# chipdesign2018.net
KiCad netlist of a schematic drawn in EAGLE
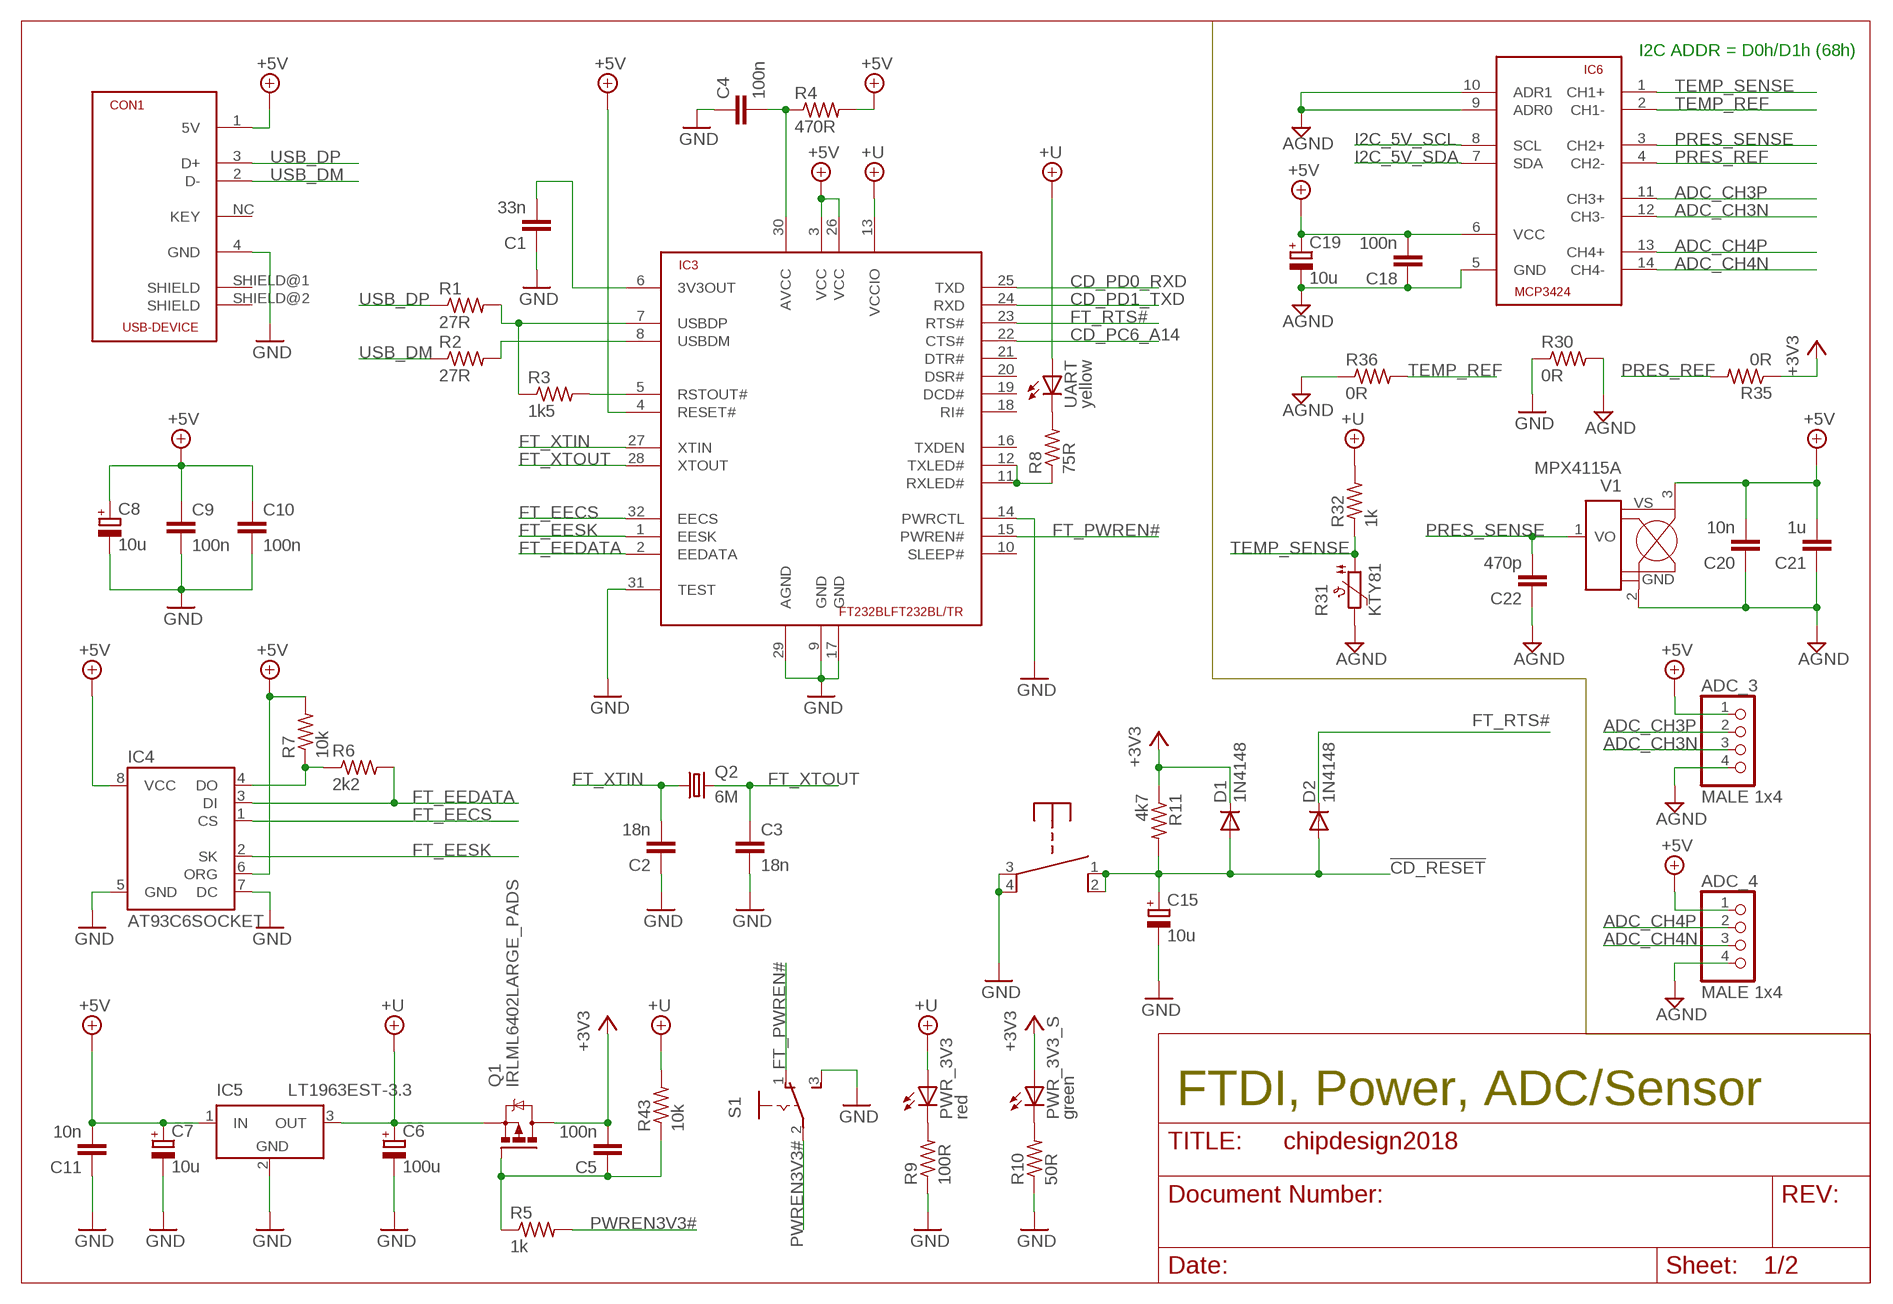
[diagram p0: schematic, sheet 1]
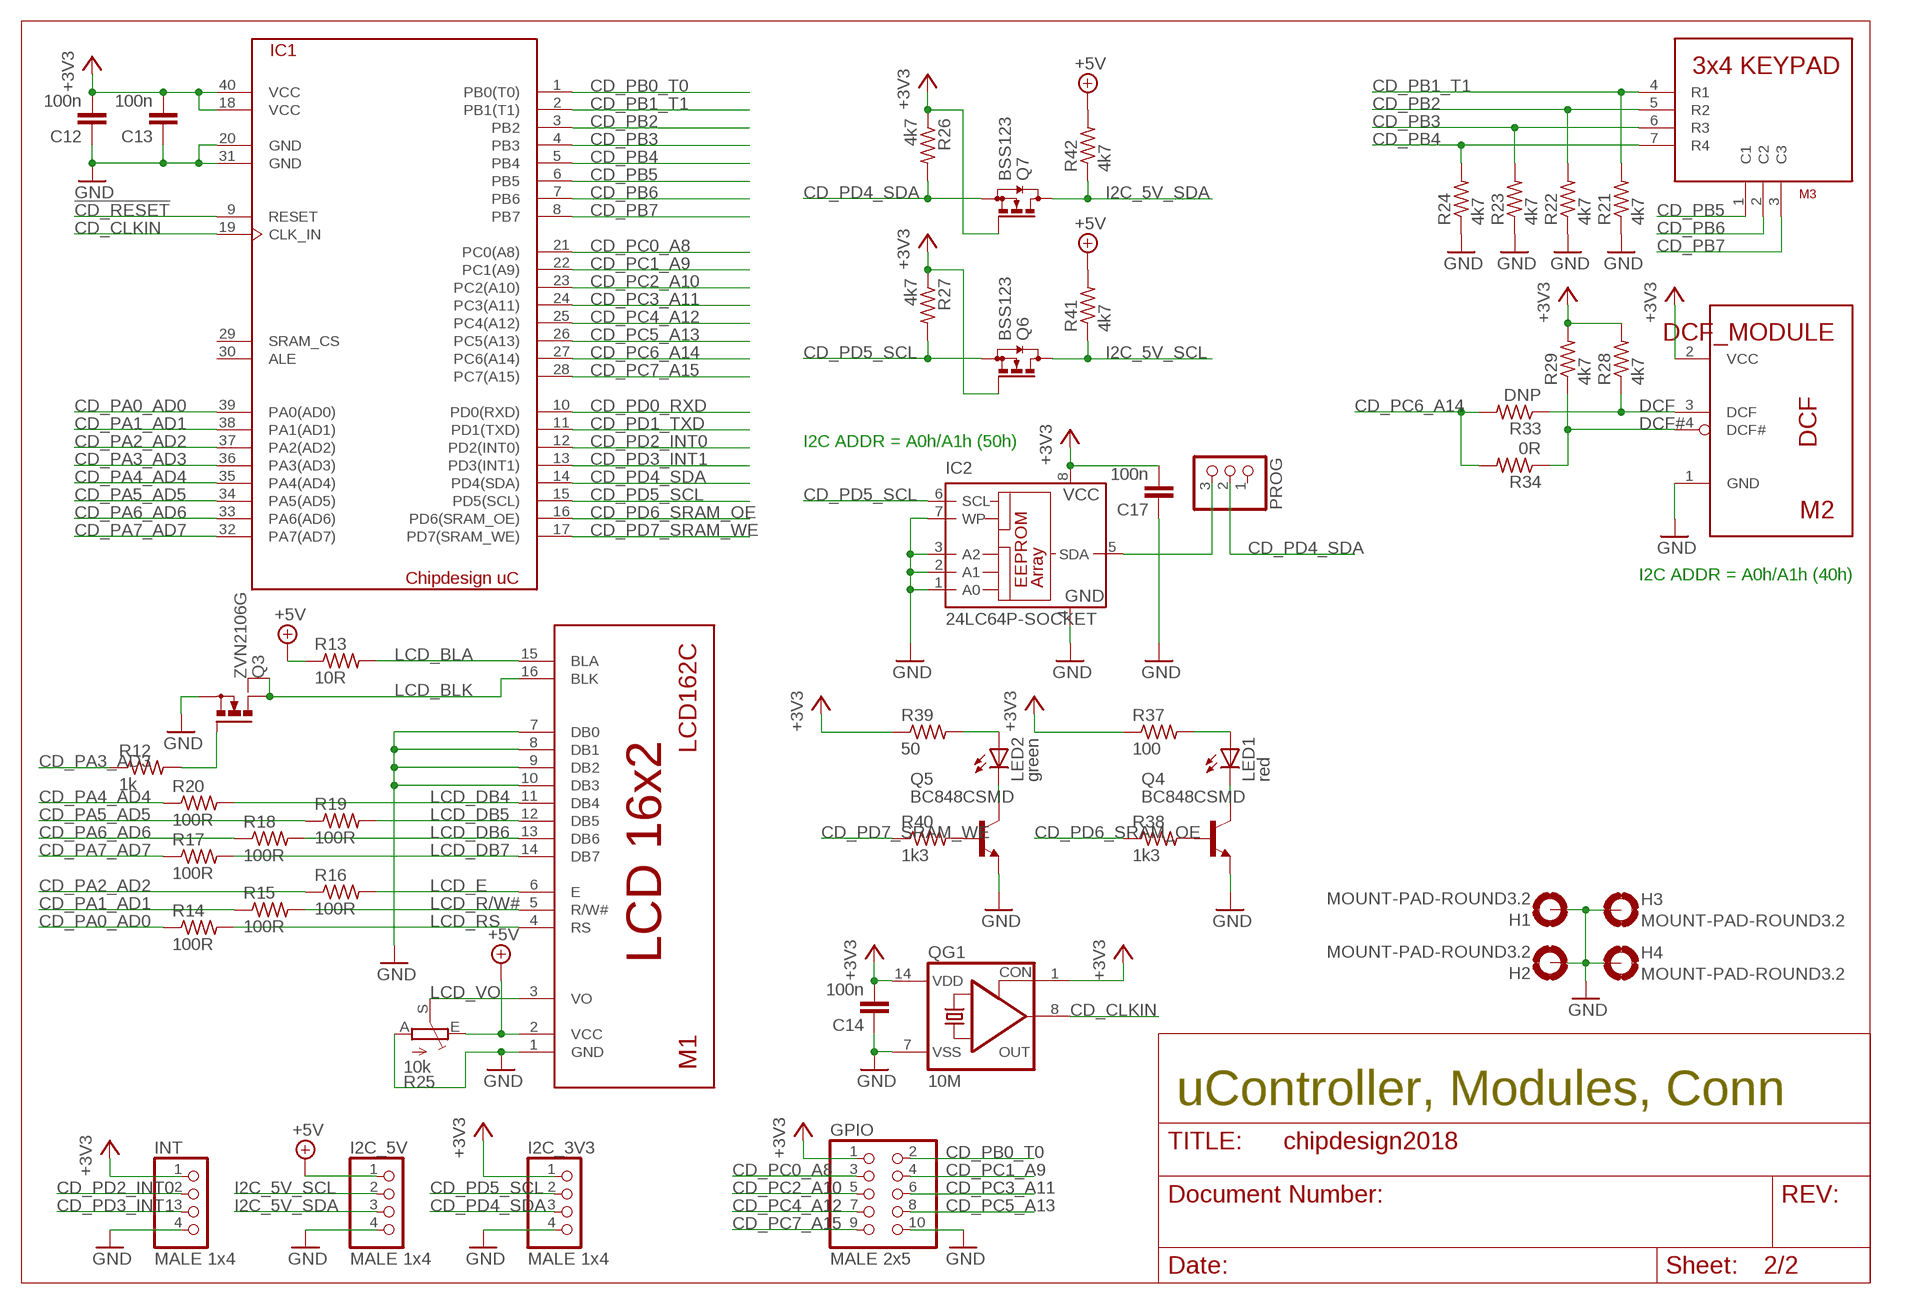
[diagram p1: schematic, sheet 2]

(export (version "E")
  (design (tool "Eeschema 10.0.6"))
  (components
    (comp (ref "ADC_3")
      (value "MALE 1x4")
      (footprint "eagle-import:1X04")
      (libsource (lib "eagle-import") (part "PINHD-1X4"))
    )
    (comp (ref "ADC_4")
      (value "MALE 1x4")
      (footprint "eagle-import:1X04")
      (libsource (lib "eagle-import") (part "PINHD-1X4"))
    )
    (comp (ref "C1")
      (value "33n")
      (footprint "eagle-import:C025-025X050")
      (libsource (lib "eagle-import") (part "C-EU025-025X050"))
    )
    (comp (ref "C2")
      (value "18n")
      (footprint "eagle-import:C025-025X050")
      (libsource (lib "eagle-import") (part "C-EU025-025X050"))
    )
    (comp (ref "C3")
      (value "18n")
      (footprint "eagle-import:C025-025X050")
      (libsource (lib "eagle-import") (part "C-EU025-025X050"))
    )
    (comp (ref "C4")
      (value "100n")
      (footprint "eagle-import:C025-025X050")
      (libsource (lib "eagle-import") (part "C-EU025-025X050"))
    )
    (comp (ref "C5")
      (value "100n")
      (footprint "eagle-import:C025-025X050")
      (libsource (lib "eagle-import") (part "C-EU025-025X050"))
    )
    (comp (ref "C6")
      (value "100u")
      (footprint "eagle-import:E2,5-6")
      (libsource (lib "eagle-import") (part "CPOL-EUE2.5-6"))
    )
    (comp (ref "C7")
      (value "10u")
      (footprint "eagle-import:E2-5")
      (libsource (lib "eagle-import") (part "CPOL-EUE2-5"))
    )
    (comp (ref "C8")
      (value "10u")
      (footprint "eagle-import:E2-5")
      (libsource (lib "eagle-import") (part "CPOL-EUE2-5"))
    )
    (comp (ref "C9")
      (value "100n")
      (footprint "eagle-import:C025-025X050")
      (libsource (lib "eagle-import") (part "C-EU025-025X050"))
    )
    (comp (ref "C10")
      (value "100n")
      (footprint "eagle-import:C025-025X050")
      (libsource (lib "eagle-import") (part "C-EU025-025X050"))
    )
    (comp (ref "C11")
      (value "10n")
      (footprint "eagle-import:C025-025X050")
      (libsource (lib "eagle-import") (part "C-EU025-025X050"))
    )
    (comp (ref "C15")
      (value "10u")
      (footprint "eagle-import:E2-5")
      (libsource (lib "eagle-import") (part "CPOL-EUE2-5"))
    )
    (comp (ref "C18")
      (value "100n")
      (footprint "eagle-import:C025-025X050")
      (libsource (lib "eagle-import") (part "C-EU025-025X050"))
    )
    (comp (ref "C19")
      (value "10u")
      (footprint "eagle-import:E2-5")
      (libsource (lib "eagle-import") (part "CPOL-EUE2-5"))
    )
    (comp (ref "C20")
      (value "10n")
      (footprint "eagle-import:C025-025X050")
      (libsource (lib "eagle-import") (part "C-EU025-025X050"))
    )
    (comp (ref "C21")
      (value "1u")
      (footprint "eagle-import:C025-025X050")
      (libsource (lib "eagle-import") (part "C-EU025-025X050"))
    )
    (comp (ref "C22")
      (value "470p")
      (footprint "eagle-import:C025-025X050")
      (libsource (lib "eagle-import") (part "C-EU025-025X050"))
    )
    (comp (ref "CON1")
      (value "USB-DEVICE")
      (footprint "eagle-import:USB-B")
      (libsource (lib "eagle-import") (part "USB-DEVICE"))
    )
    (comp (ref "D1")
      (value "1N4148")
      (footprint "eagle-import:DO35-7")
      (libsource (lib "eagle-import") (part "1N4148DO35-7"))
    )
    (comp (ref "D2")
      (value "1N4148")
      (footprint "eagle-import:DO35-7")
      (libsource (lib "eagle-import") (part "1N4148DO35-7"))
    )
    (comp (ref "IC3")
      (value "FT232BLFT232BL/TR")
      (footprint "eagle-import:LQFP-32")
      (libsource (lib "eagle-import") (part "FT232BLFT232BL/TR"))
    )
    (comp (ref "IC4")
      (value "AT93C6SOCKET")
      (footprint "eagle-import:SOCKET-08")
      (libsource (lib "eagle-import") (part "AT93C6SOCKET"))
    )
    (comp (ref "IC5")
      (value "LT1963EST-3.3")
      (footprint "eagle-import:SOT223")
      (libsource (lib "eagle-import") (part "LT1963EST-3.3"))
    )
    (comp (ref "IC6")
      (value "MCP3424")
      (footprint "eagle-import:SO-14")
      (libsource (lib "eagle-import") (part "MCP3424"))
    )
    (comp (ref "PWR_3V3")
      (value "red")
      (footprint "eagle-import:LED3MM")
      (libsource (lib "eagle-import") (part "LED3MM"))
    )
    (comp (ref "PWR_3V3_S")
      (value "green")
      (footprint "eagle-import:LED3MM")
      (libsource (lib "eagle-import") (part "LED3MM"))
    )
    (comp (ref "Q1")
      (value "IRLML6402LARGE_PADS")
      (footprint "eagle-import:SOT23W_INFINEON")
      (libsource (lib "eagle-import") (part "IRLML6402LARGE_PADS"))
    )
    (comp (ref "Q2")
      (value "6M")
      (footprint "eagle-import:HC49_S")
      (libsource (lib "eagle-import") (part "CRYSTALHC49S"))
    )
    (comp (ref "R1")
      (value "27R")
      (footprint "eagle-import:0207_7")
      (libsource (lib "eagle-import") (part "R-US_0207/7"))
    )
    (comp (ref "R2")
      (value "27R")
      (footprint "eagle-import:0207_7")
      (libsource (lib "eagle-import") (part "R-US_0207/7"))
    )
    (comp (ref "R3")
      (value "1k5")
      (footprint "eagle-import:0207_7")
      (libsource (lib "eagle-import") (part "R-US_0207/7"))
    )
    (comp (ref "R4")
      (value "470R")
      (footprint "eagle-import:0207_7")
      (libsource (lib "eagle-import") (part "R-US_0207/7"))
    )
    (comp (ref "R5")
      (value "1k")
      (footprint "eagle-import:0207_7")
      (libsource (lib "eagle-import") (part "R-US_0207/7"))
    )
    (comp (ref "R6")
      (value "2k2")
      (footprint "eagle-import:0207_7")
      (libsource (lib "eagle-import") (part "R-US_0207/7"))
    )
    (comp (ref "R7")
      (value "10k")
      (footprint "eagle-import:0207_7")
      (libsource (lib "eagle-import") (part "R-US_0207/7"))
    )
    (comp (ref "R8")
      (value "75R")
      (footprint "eagle-import:0207_7")
      (libsource (lib "eagle-import") (part "R-US_0207/7"))
    )
    (comp (ref "R9")
      (value "100R")
      (footprint "eagle-import:0207_7")
      (libsource (lib "eagle-import") (part "R-US_0207/7"))
    )
    (comp (ref "R10")
      (value "50R")
      (footprint "eagle-import:0207_7")
      (libsource (lib "eagle-import") (part "R-US_0207/7"))
    )
    (comp (ref "R11")
      (value "4k7")
      (footprint "eagle-import:0207_7")
      (libsource (lib "eagle-import") (part "R-US_0207/7"))
    )
    (comp (ref "R30")
      (value "0R")
      (footprint "eagle-import:0207_7")
      (libsource (lib "eagle-import") (part "R-US_0207/7"))
    )
    (comp (ref "R31")
      (value "KTY81")
      (footprint "eagle-import:SOD70")
      (libsource (lib "eagle-import") (part "PTC-SOD70"))
    )
    (comp (ref "R32")
      (value "1k")
      (footprint "eagle-import:0207_7")
      (libsource (lib "eagle-import") (part "R-US_0207/7"))
    )
    (comp (ref "R35")
      (value "0R")
      (footprint "eagle-import:0207_7")
      (libsource (lib "eagle-import") (part "R-US_0207/7"))
    )
    (comp (ref "R36")
      (value "0R")
      (footprint "eagle-import:0207_7")
      (libsource (lib "eagle-import") (part "R-US_0207/7"))
    )
    (comp (ref "R43")
      (value "10k")
      (footprint "eagle-import:0207_7")
      (libsource (lib "eagle-import") (part "R-US_0207/7"))
    )
    (comp (ref "S1")
      (value "255SB")
      (footprint "eagle-import:255SB")
      (libsource (lib "eagle-import") (part "255SB"))
    )
    (comp (ref "U$1")
      (value "PHAP3301")
      (footprint "eagle-import:PHAP3301")
      (libsource (lib "eagle-import") (part "PHAP3301"))
    )
    (comp (ref "UART")
      (value "yellow")
      (footprint "eagle-import:LED3MM")
      (libsource (lib "eagle-import") (part "LED3MM"))
    )
    (comp (ref "V1")
      (value "MPX4115A")
      (footprint "eagle-import:MPX_CASE867")
      (libsource (lib "eagle-import") (part "MPX4250A"))
    )
    (comp (ref "C12")
      (value "100n")
      (footprint "eagle-import:C025-025X050")
      (libsource (lib "eagle-import") (part "C-EU025-025X050"))
    )
    (comp (ref "C13")
      (value "100n")
      (footprint "eagle-import:C025-025X050")
      (libsource (lib "eagle-import") (part "C-EU025-025X050"))
    )
    (comp (ref "C14")
      (value "100n")
      (footprint "eagle-import:C025-025X050")
      (libsource (lib "eagle-import") (part "C-EU025-025X050"))
    )
    (comp (ref "C17")
      (value "100n")
      (footprint "eagle-import:C025-025X050")
      (libsource (lib "eagle-import") (part "C-EU025-025X050"))
    )
    (comp (ref "GPIO")
      (value "MALE 2x5")
      (footprint "eagle-import:2X05")
      (libsource (lib "eagle-import") (part "PINHD-2X5"))
    )
    (comp (ref "H1")
      (value "MOUNT-PAD-ROUND3.2")
      (footprint "eagle-import:3,2-PAD")
      (libsource (lib "eagle-import") (part "MOUNT-PAD-ROUND3.2"))
    )
    (comp (ref "H2")
      (value "MOUNT-PAD-ROUND3.2")
      (footprint "eagle-import:3,2-PAD")
      (libsource (lib "eagle-import") (part "MOUNT-PAD-ROUND3.2"))
    )
    (comp (ref "H3")
      (value "MOUNT-PAD-ROUND3.2")
      (footprint "eagle-import:3,2-PAD")
      (libsource (lib "eagle-import") (part "MOUNT-PAD-ROUND3.2"))
    )
    (comp (ref "H4")
      (value "MOUNT-PAD-ROUND3.2")
      (footprint "eagle-import:3,2-PAD")
      (libsource (lib "eagle-import") (part "MOUNT-PAD-ROUND3.2"))
    )
    (comp (ref "I2C_3V3")
      (value "MALE 1x4")
      (footprint "eagle-import:1X04")
      (libsource (lib "eagle-import") (part "PINHD-1X4"))
    )
    (comp (ref "I2C_5V")
      (value "MALE 1x4")
      (footprint "eagle-import:1X04")
      (libsource (lib "eagle-import") (part "PINHD-1X4"))
    )
    (comp (ref "IC1")
      (value "Chipdesign uC")
      (footprint "eagle-import:FPGA-BOARD-2X20")
      (libsource (lib "eagle-import") (part "CHIPDESIGN_UC"))
    )
    (comp (ref "IC2")
      (value "24LC64P-SOCKET")
      (footprint "eagle-import:SOCKET-08")
      (fields (field (name "MF") "MICROCHIP") (field (name "MPN") "24LC64-I/P"))
      (libsource (lib "eagle-import") (part "24P-SOCKETLC64"))
    )
    (comp (ref "INT")
      (value "MALE 1x4")
      (footprint "eagle-import:1X04")
      (libsource (lib "eagle-import") (part "PINHD-1X4"))
    )
    (comp (ref "LED1")
      (value "red")
      (footprint "eagle-import:LED3MM")
      (libsource (lib "eagle-import") (part "LED3MM"))
    )
    (comp (ref "LED2")
      (value "green")
      (footprint "eagle-import:LED3MM")
      (libsource (lib "eagle-import") (part "LED3MM"))
    )
    (comp (ref "M1")
      (value "LCD162C")
      (footprint "eagle-import:LCD162C")
      (libsource (lib "eagle-import") (part "LCD162C"))
    )
    (comp (ref "M2")
      (value "DCF_MODULE")
      (footprint "eagle-import:DCF_MODULE")
      (libsource (lib "eagle-import") (part "DCF_MODULE"))
    )
    (comp (ref "M3")
      (value "KEYPAD")
      (footprint "eagle-import:KEYPAD")
      (libsource (lib "eagle-import") (part "KEYPAD"))
    )
    (comp (ref "PROG")
      (value "PINHD-1X3")
      (footprint "eagle-import:1X03")
      (libsource (lib "eagle-import") (part "PINHD-1X3"))
    )
    (comp (ref "Q3")
      (value "ZVN2106G")
      (footprint "eagle-import:SOT223")
      (libsource (lib "eagle-import") (part "ZVN2106G"))
    )
    (comp (ref "Q4")
      (value "BC848CSMD")
      (footprint "eagle-import:SOT23")
      (libsource (lib "eagle-import") (part "BC848SMDC"))
    )
    (comp (ref "Q5")
      (value "BC848CSMD")
      (footprint "eagle-import:SOT23")
      (libsource (lib "eagle-import") (part "BC848SMDC"))
    )
    (comp (ref "Q6")
      (value "BSS123")
      (footprint "eagle-import:SOT23")
      (libsource (lib "eagle-import") (part "BSS123"))
    )
    (comp (ref "Q7")
      (value "BSS123")
      (footprint "eagle-import:SOT23")
      (libsource (lib "eagle-import") (part "BSS123"))
    )
    (comp (ref "QG1")
      (value "10M")
      (footprint "eagle-import:SG51")
      (libsource (lib "eagle-import") (part "CRYSTAL_RES-SG51"))
    )
    (comp (ref "R12")
      (value "1k")
      (footprint "eagle-import:0207_7")
      (libsource (lib "eagle-import") (part "R-US_0207/7"))
    )
    (comp (ref "R13")
      (value "10R")
      (footprint "eagle-import:0207_7")
      (libsource (lib "eagle-import") (part "R-US_0207/7"))
    )
    (comp (ref "R14")
      (value "100R")
      (footprint "eagle-import:0207_7")
      (libsource (lib "eagle-import") (part "R-US_0207/7"))
    )
    (comp (ref "R15")
      (value "100R")
      (footprint "eagle-import:0207_7")
      (libsource (lib "eagle-import") (part "R-US_0207/7"))
    )
    (comp (ref "R16")
      (value "100R")
      (footprint "eagle-import:0207_7")
      (libsource (lib "eagle-import") (part "R-US_0207/7"))
    )
    (comp (ref "R17")
      (value "100R")
      (footprint "eagle-import:0207_7")
      (libsource (lib "eagle-import") (part "R-US_0207/7"))
    )
    (comp (ref "R18")
      (value "100R")
      (footprint "eagle-import:0207_7")
      (libsource (lib "eagle-import") (part "R-US_0207/7"))
    )
    (comp (ref "R19")
      (value "100R")
      (footprint "eagle-import:0207_7")
      (libsource (lib "eagle-import") (part "R-US_0207/7"))
    )
    (comp (ref "R20")
      (value "100R")
      (footprint "eagle-import:0207_7")
      (libsource (lib "eagle-import") (part "R-US_0207/7"))
    )
    (comp (ref "R21")
      (value "4k7")
      (footprint "eagle-import:0207_7")
      (libsource (lib "eagle-import") (part "R-US_0207/7"))
    )
    (comp (ref "R22")
      (value "4k7")
      (footprint "eagle-import:0207_7")
      (libsource (lib "eagle-import") (part "R-US_0207/7"))
    )
    (comp (ref "R23")
      (value "4k7")
      (footprint "eagle-import:0207_7")
      (libsource (lib "eagle-import") (part "R-US_0207/7"))
    )
    (comp (ref "R24")
      (value "4k7")
      (footprint "eagle-import:0207_7")
      (libsource (lib "eagle-import") (part "R-US_0207/7"))
    )
    (comp (ref "R25")
      (value "10k")
      (footprint "eagle-import:ST6")
      (libsource (lib "eagle-import") (part "TRIM_EU-"))
    )
    (comp (ref "R26")
      (value "4k7")
      (footprint "eagle-import:0207_7")
      (libsource (lib "eagle-import") (part "R-US_0207/7"))
    )
    (comp (ref "R27")
      (value "4k7")
      (footprint "eagle-import:0207_7")
      (libsource (lib "eagle-import") (part "R-US_0207/7"))
    )
    (comp (ref "R28")
      (value "4k7")
      (footprint "eagle-import:0207_7")
      (libsource (lib "eagle-import") (part "R-US_0207/7"))
    )
    (comp (ref "R29")
      (value "4k7")
      (footprint "eagle-import:0207_7")
      (libsource (lib "eagle-import") (part "R-US_0207/7"))
    )
    (comp (ref "R33")
      (value "DNP")
      (footprint "eagle-import:0207_7")
      (libsource (lib "eagle-import") (part "R-US_0207/7"))
    )
    (comp (ref "R34")
      (value "0R")
      (footprint "eagle-import:0207_7")
      (libsource (lib "eagle-import") (part "R-US_0207/7"))
    )
    (comp (ref "R37")
      (value "100")
      (footprint "eagle-import:0207_7")
      (libsource (lib "eagle-import") (part "R-US_0207/7"))
    )
    (comp (ref "R38")
      (value "1k3")
      (footprint "eagle-import:0207_7")
      (libsource (lib "eagle-import") (part "R-US_0207/7"))
    )
    (comp (ref "R39")
      (value "50")
      (footprint "eagle-import:0207_7")
      (libsource (lib "eagle-import") (part "R-US_0207/7"))
    )
    (comp (ref "R40")
      (value "1k3")
      (footprint "eagle-import:0207_7")
      (libsource (lib "eagle-import") (part "R-US_0207/7"))
    )
    (comp (ref "R41")
      (value "4k7")
      (footprint "eagle-import:0207_7")
      (libsource (lib "eagle-import") (part "R-US_0207/7"))
    )
    (comp (ref "R42")
      (value "4k7")
      (footprint "eagle-import:0207_7")
      (libsource (lib "eagle-import") (part "R-US_0207/7"))
    )
  )
  (nets
    (net (code "1") (name "+3V3") (class "Default")
      (node (ref "C12") (pin "2") (pinfunction "2_2") (pintype "passive"))
      (node (ref "C13") (pin "2") (pinfunction "2_2") (pintype "passive"))
      (node (ref "C14") (pin "2") (pinfunction "2_2") (pintype "passive"))
      (node (ref "C17") (pin "2") (pinfunction "2_2") (pintype "passive"))
      (node (ref "C5") (pin "2") (pinfunction "2_2") (pintype "passive"))
      (node (ref "D1") (pin "C") (pinfunction "C_C") (pintype "passive"))
      (node (ref "GPIO") (pin "1") (pinfunction "1_1") (pintype "passive"))
      (node (ref "I2C_3V3") (pin "1") (pinfunction "1_1") (pintype "passive"))
      (node (ref "IC1") (pin "18") (pinfunction "VCC_18") (pintype "power_in"))
      (node (ref "IC1") (pin "40") (pinfunction "VCC_40") (pintype "power_in"))
      (node (ref "IC2") (pin "8") (pinfunction "VCC_8") (pintype "power_in"))
      (node (ref "INT") (pin "1") (pinfunction "1_1") (pintype "passive"))
      (node (ref "M2") (pin "2") (pinfunction "VCC_2") (pintype "power_in"))
      (node (ref "PWR_3V3_S") (pin "A") (pinfunction "A_A") (pintype "passive"))
      (node (ref "Q1") (pin "3") (pinfunction "D_3") (pintype "passive"))
      (node (ref "Q6") (pin "1") (pinfunction "G_1") (pintype "passive"))
      (node (ref "Q7") (pin "1") (pinfunction "G_1") (pintype "passive"))
      (node (ref "QG1") (pin "1") (pinfunction "CON_1") (pintype "input"))
      (node (ref "QG1") (pin "14") (pinfunction "VDD_14") (pintype "power_in"))
      (node (ref "R11") (pin "1") (pinfunction "1_1") (pintype "passive"))
      (node (ref "R26") (pin "1") (pinfunction "1_1") (pintype "passive"))
      (node (ref "R27") (pin "1") (pinfunction "1_1") (pintype "passive"))
      (node (ref "R28") (pin "2") (pinfunction "2_2") (pintype "passive"))
      (node (ref "R29") (pin "2") (pinfunction "2_2") (pintype "passive"))
      (node (ref "R35") (pin "1") (pinfunction "1_1") (pintype "passive"))
      (node (ref "R37") (pin "1") (pinfunction "1_1") (pintype "passive"))
      (node (ref "R39") (pin "1") (pinfunction "1_1") (pintype "passive"))
    )
    (net (code "2") (name "+5V") (class "Default")
      (node (ref "ADC_3") (pin "1") (pinfunction "1_1") (pintype "passive"))
      (node (ref "ADC_4") (pin "1") (pinfunction "1_1") (pintype "passive"))
      (node (ref "C10") (pin "1") (pinfunction "1_1") (pintype "passive"))
      (node (ref "C11") (pin "2") (pinfunction "2_2") (pintype "passive"))
      (node (ref "C18") (pin "2") (pinfunction "2_2") (pintype "passive"))
      (node (ref "C19") (pin "+") (pinfunction "+_+") (pintype "passive"))
      (node (ref "C20") (pin "2") (pinfunction "2_2") (pintype "passive"))
      (node (ref "C21") (pin "2") (pinfunction "2_2") (pintype "passive"))
      (node (ref "C7") (pin "+") (pinfunction "+_+") (pintype "passive"))
      (node (ref "C8") (pin "+") (pinfunction "+_+") (pintype "passive"))
      (node (ref "C9") (pin "1") (pinfunction "1_1") (pintype "passive"))
      (node (ref "CON1") (pin "1") (pinfunction "5V_1") (pintype "power_in"))
      (node (ref "I2C_5V") (pin "1") (pinfunction "1_1") (pintype "passive"))
      (node (ref "IC3") (pin "26") (pinfunction "VCC_26") (pintype "power_in"))
      (node (ref "IC3") (pin "3") (pinfunction "VCC_3") (pintype "power_in"))
      (node (ref "IC3") (pin "4") (pinfunction "RESET#_4") (pintype "bidirectional"))
      (node (ref "IC4") (pin "6") (pinfunction "ORG_6") (pintype "input"))
      (node (ref "IC4") (pin "8") (pinfunction "VCC_8") (pintype "power_in"))
      (node (ref "IC5") (pin "1") (pinfunction "IN_1") (pintype "input"))
      (node (ref "IC6") (pin "6") (pinfunction "VCC_6") (pintype "power_in"))
      (node (ref "M1") (pin "2") (pinfunction "VCC_2") (pintype "power_in"))
      (node (ref "R13") (pin "1") (pinfunction "1_1") (pintype "passive"))
      (node (ref "R25") (pin "E") (pinfunction "E_E") (pintype "passive"))
      (node (ref "R4") (pin "2") (pinfunction "2_2") (pintype "passive"))
      (node (ref "R41") (pin "2") (pinfunction "2_2") (pintype "passive"))
      (node (ref "R42") (pin "2") (pinfunction "2_2") (pintype "passive"))
      (node (ref "R7") (pin "2") (pinfunction "2_2") (pintype "passive"))
      (node (ref "V1") (pin "3") (pinfunction "VS_3") (pintype "passive"))
    )
    (net (code "3") (name "+UB") (class "Default")
      (node (ref "C6") (pin "+") (pinfunction "+_+") (pintype "passive"))
      (node (ref "IC3") (pin "13") (pinfunction "VCCIO_13") (pintype "power_in"))
      (node (ref "IC5") (pin "3") (pinfunction "OUT_3") (pintype "output"))
      (node (ref "PWR_3V3") (pin "A") (pinfunction "A_A") (pintype "passive"))
      (node (ref "Q1") (pin "2") (pinfunction "S_2") (pintype "passive"))
      (node (ref "R32") (pin "2") (pinfunction "2_2") (pintype "passive"))
      (node (ref "R43") (pin "2") (pinfunction "2_2") (pintype "passive"))
      (node (ref "UART") (pin "A") (pinfunction "A_A") (pintype "passive"))
    )
    (net (code "4") (name "ADC_CH3N") (class "Default")
      (node (ref "ADC_3") (pin "3") (pinfunction "3_3") (pintype "passive"))
      (node (ref "IC6") (pin "12") (pinfunction "CH3-_12") (pintype "bidirectional"))
    )
    (net (code "5") (name "ADC_CH3P") (class "Default")
      (node (ref "ADC_3") (pin "2") (pinfunction "2_2") (pintype "passive"))
      (node (ref "IC6") (pin "11") (pinfunction "CH3+_11") (pintype "bidirectional"))
    )
    (net (code "6") (name "ADC_CH4N") (class "Default")
      (node (ref "ADC_4") (pin "3") (pinfunction "3_3") (pintype "passive"))
      (node (ref "IC6") (pin "14") (pinfunction "CH4-_14") (pintype "bidirectional"))
    )
    (net (code "7") (name "ADC_CH4P") (class "Default")
      (node (ref "ADC_4") (pin "2") (pinfunction "2_2") (pintype "passive"))
      (node (ref "IC6") (pin "13") (pinfunction "CH4+_13") (pintype "bidirectional"))
    )
    (net (code "8") (name "AGND") (class "Default")
      (node (ref "ADC_3") (pin "4") (pinfunction "4_4") (pintype "passive"))
      (node (ref "ADC_4") (pin "4") (pinfunction "4_4") (pintype "passive"))
      (node (ref "C18") (pin "1") (pinfunction "1_1") (pintype "passive"))
      (node (ref "C19") (pin "-") (pinfunction "-_-") (pintype "passive"))
      (node (ref "C20") (pin "1") (pinfunction "1_1") (pintype "passive"))
      (node (ref "C21") (pin "1") (pinfunction "1_1") (pintype "passive"))
      (node (ref "C22") (pin "1") (pinfunction "1_1") (pintype "passive"))
      (node (ref "IC6") (pin "10") (pinfunction "ADR1_10") (pintype "input"))
      (node (ref "IC6") (pin "5") (pinfunction "GND_5") (pintype "power_in"))
      (node (ref "IC6") (pin "9") (pinfunction "ADR0_9") (pintype "input"))
      (node (ref "R30") (pin "2") (pinfunction "2_2") (pintype "passive"))
      (node (ref "R31") (pin "2") (pinfunction "2_2") (pintype "passive"))
      (node (ref "R36") (pin "1") (pinfunction "1_1") (pintype "passive"))
      (node (ref "V1") (pin "2") (pinfunction "GND_2") (pintype "passive"))
    )
    (net (code "9") (name "CD_CLKIN") (class "Default")
      (node (ref "IC1") (pin "19") (pinfunction "CLK_IN_19") (pintype "input"))
      (node (ref "QG1") (pin "8") (pinfunction "OUT_8") (pintype "output"))
    )
    (net (code "10") (name "CD_PA0_AD0") (class "Default")
      (node (ref "IC1") (pin "39") (pinfunction "PA0(AD0)_39") (pintype "bidirectional"))
      (node (ref "R14") (pin "1") (pinfunction "1_1") (pintype "passive"))
    )
    (net (code "11") (name "CD_PA1_AD1") (class "Default")
      (node (ref "IC1") (pin "38") (pinfunction "PA1(AD1)_38") (pintype "bidirectional"))
      (node (ref "R15") (pin "1") (pinfunction "1_1") (pintype "passive"))
    )
    (net (code "12") (name "CD_PA2_AD2") (class "Default")
      (node (ref "IC1") (pin "37") (pinfunction "PA2(AD2)_37") (pintype "bidirectional"))
      (node (ref "R16") (pin "1") (pinfunction "1_1") (pintype "passive"))
    )
    (net (code "13") (name "CD_PA3_AD3") (class "Default")
      (node (ref "IC1") (pin "36") (pinfunction "PA3(AD3)_36") (pintype "bidirectional"))
      (node (ref "R12") (pin "1") (pinfunction "1_1") (pintype "passive"))
    )
    (net (code "14") (name "CD_PA4_AD4") (class "Default")
      (node (ref "IC1") (pin "35") (pinfunction "PA4(AD4)_35") (pintype "bidirectional"))
      (node (ref "R20") (pin "1") (pinfunction "1_1") (pintype "passive"))
    )
    (net (code "15") (name "CD_PA5_AD5") (class "Default")
      (node (ref "IC1") (pin "34") (pinfunction "PA5(AD5)_34") (pintype "bidirectional"))
      (node (ref "R19") (pin "1") (pinfunction "1_1") (pintype "passive"))
    )
    (net (code "16") (name "CD_PA6_AD6") (class "Default")
      (node (ref "IC1") (pin "33") (pinfunction "PA6(AD6)_33") (pintype "bidirectional"))
      (node (ref "R18") (pin "1") (pinfunction "1_1") (pintype "passive"))
    )
    (net (code "17") (name "CD_PA7_AD7") (class "Default")
      (node (ref "IC1") (pin "32") (pinfunction "PA7(AD7)_32") (pintype "bidirectional"))
      (node (ref "R17") (pin "1") (pinfunction "1_1") (pintype "passive"))
    )
    (net (code "18") (name "CD_PB0_T0") (class "Default")
      (node (ref "GPIO") (pin "2") (pinfunction "2_2") (pintype "passive"))
      (node (ref "IC1") (pin "1") (pinfunction "PB0(T0)_1") (pintype "bidirectional"))
    )
    (net (code "19") (name "CD_PB1_T1") (class "Default")
      (node (ref "IC1") (pin "2") (pinfunction "PB1(T1)_2") (pintype "bidirectional"))
      (node (ref "M3") (pin "4") (pinfunction "R1_4") (pintype "bidirectional"))
      (node (ref "R21") (pin "2") (pinfunction "2_2") (pintype "passive"))
    )
    (net (code "20") (name "CD_PB2") (class "Default")
      (node (ref "IC1") (pin "3") (pinfunction "PB2_3") (pintype "bidirectional"))
      (node (ref "M3") (pin "5") (pinfunction "R2_5") (pintype "bidirectional"))
      (node (ref "R22") (pin "2") (pinfunction "2_2") (pintype "passive"))
    )
    (net (code "21") (name "CD_PB3") (class "Default")
      (node (ref "IC1") (pin "4") (pinfunction "PB3_4") (pintype "bidirectional"))
      (node (ref "M3") (pin "6") (pinfunction "R3_6") (pintype "bidirectional"))
      (node (ref "R23") (pin "2") (pinfunction "2_2") (pintype "passive"))
    )
    (net (code "22") (name "CD_PB4") (class "Default")
      (node (ref "IC1") (pin "5") (pinfunction "PB4_5") (pintype "bidirectional"))
      (node (ref "M3") (pin "7") (pinfunction "R4_7") (pintype "bidirectional"))
      (node (ref "R24") (pin "2") (pinfunction "2_2") (pintype "passive"))
    )
    (net (code "23") (name "CD_PB5") (class "Default")
      (node (ref "IC1") (pin "6") (pinfunction "PB5_6") (pintype "bidirectional"))
      (node (ref "M3") (pin "1") (pinfunction "C1_1") (pintype "bidirectional"))
    )
    (net (code "24") (name "CD_PB6") (class "Default")
      (node (ref "IC1") (pin "7") (pinfunction "PB6_7") (pintype "bidirectional"))
      (node (ref "M3") (pin "2") (pinfunction "C2_2") (pintype "bidirectional"))
    )
    (net (code "25") (name "CD_PB7") (class "Default")
      (node (ref "IC1") (pin "8") (pinfunction "PB7_8") (pintype "bidirectional"))
      (node (ref "M3") (pin "3") (pinfunction "C3_3") (pintype "bidirectional"))
    )
    (net (code "26") (name "CD_PC0_A8") (class "Default")
      (node (ref "GPIO") (pin "3") (pinfunction "3_3") (pintype "passive"))
      (node (ref "IC1") (pin "21") (pinfunction "PC0(A8)_21") (pintype "bidirectional"))
    )
    (net (code "27") (name "CD_PC1_A9") (class "Default")
      (node (ref "GPIO") (pin "4") (pinfunction "4_4") (pintype "passive"))
      (node (ref "IC1") (pin "22") (pinfunction "PC1(A9)_22") (pintype "bidirectional"))
    )
    (net (code "28") (name "CD_PC2_A10") (class "Default")
      (node (ref "GPIO") (pin "5") (pinfunction "5_5") (pintype "passive"))
      (node (ref "IC1") (pin "23") (pinfunction "PC2(A10)_23") (pintype "bidirectional"))
    )
    (net (code "29") (name "CD_PC3_A11") (class "Default")
      (node (ref "GPIO") (pin "6") (pinfunction "6_6") (pintype "passive"))
      (node (ref "IC1") (pin "24") (pinfunction "PC3(A11)_24") (pintype "bidirectional"))
    )
    (net (code "30") (name "CD_PC4_A12") (class "Default")
      (node (ref "GPIO") (pin "7") (pinfunction "7_7") (pintype "passive"))
      (node (ref "IC1") (pin "25") (pinfunction "PC4(A12)_25") (pintype "bidirectional"))
    )
    (net (code "31") (name "CD_PC5_A13") (class "Default")
      (node (ref "GPIO") (pin "8") (pinfunction "8_8") (pintype "passive"))
      (node (ref "IC1") (pin "26") (pinfunction "PC5(A13)_26") (pintype "bidirectional"))
    )
    (net (code "32") (name "CD_PC6_A14") (class "Default")
      (node (ref "IC1") (pin "27") (pinfunction "PC6(A14)_27") (pintype "bidirectional"))
      (node (ref "IC3") (pin "22") (pinfunction "CTS#_22") (pintype "bidirectional"))
      (node (ref "R33") (pin "2") (pinfunction "2_2") (pintype "passive"))
      (node (ref "R34") (pin "2") (pinfunction "2_2") (pintype "passive"))
    )
    (net (code "33") (name "CD_PC7_A15") (class "Default")
      (node (ref "GPIO") (pin "9") (pinfunction "9_9") (pintype "passive"))
      (node (ref "IC1") (pin "28") (pinfunction "PC7(A15)_28") (pintype "bidirectional"))
    )
    (net (code "34") (name "CD_PD0_RXD") (class "Default")
      (node (ref "IC1") (pin "10") (pinfunction "PD0(RXD)_10") (pintype "bidirectional"))
      (node (ref "IC3") (pin "25") (pinfunction "TXD_25") (pintype "bidirectional"))
    )
    (net (code "35") (name "CD_PD1_TXD") (class "Default")
      (node (ref "IC1") (pin "11") (pinfunction "PD1(TXD)_11") (pintype "bidirectional"))
      (node (ref "IC3") (pin "24") (pinfunction "RXD_24") (pintype "bidirectional"))
    )
    (net (code "36") (name "CD_PD2_INT0") (class "Default")
      (node (ref "IC1") (pin "12") (pinfunction "PD2(INT0)_12") (pintype "bidirectional"))
      (node (ref "INT") (pin "2") (pinfunction "2_2") (pintype "passive"))
    )
    (net (code "37") (name "CD_PD3_INT1") (class "Default")
      (node (ref "IC1") (pin "13") (pinfunction "PD3(INT1)_13") (pintype "bidirectional"))
      (node (ref "INT") (pin "3") (pinfunction "3_3") (pintype "passive"))
    )
    (net (code "38") (name "CD_PD4_SDA") (class "Default")
      (node (ref "I2C_3V3") (pin "3") (pinfunction "3_3") (pintype "passive"))
      (node (ref "IC1") (pin "14") (pinfunction "PD4(SDA)_14") (pintype "bidirectional"))
      (node (ref "PROG") (pin "2") (pinfunction "2_2") (pintype "passive"))
      (node (ref "Q7") (pin "2") (pinfunction "S_2") (pintype "passive"))
      (node (ref "R26") (pin "2") (pinfunction "2_2") (pintype "passive"))
    )
    (net (code "39") (name "CD_PD5_SCL") (class "Default")
      (node (ref "I2C_3V3") (pin "2") (pinfunction "2_2") (pintype "passive"))
      (node (ref "IC1") (pin "15") (pinfunction "PD5(SCL)_15") (pintype "bidirectional"))
      (node (ref "IC2") (pin "6") (pinfunction "SCL_6") (pintype "input"))
      (node (ref "Q6") (pin "2") (pinfunction "S_2") (pintype "passive"))
      (node (ref "R27") (pin "2") (pinfunction "2_2") (pintype "passive"))
    )
    (net (code "40") (name "CD_PD6_SRAM_OE") (class "Default")
      (node (ref "IC1") (pin "16") (pinfunction "PD6(SRAM_OE)_16") (pintype "bidirectional"))
      (node (ref "R38") (pin "1") (pinfunction "1_1") (pintype "passive"))
    )
    (net (code "41") (name "CD_PD7_SRAM_WE") (class "Default")
      (node (ref "IC1") (pin "17") (pinfunction "PD7(SRAM_WE)_17") (pintype "bidirectional"))
      (node (ref "R40") (pin "1") (pinfunction "1_1") (pintype "passive"))
    )
    (net (code "42") (name "DCF") (class "Default")
      (node (ref "M2") (pin "3") (pinfunction "DCF_3") (pintype "output"))
      (node (ref "R28") (pin "1") (pinfunction "1_1") (pintype "passive"))
      (node (ref "R33") (pin "1") (pinfunction "1_1") (pintype "passive"))
    )
    (net (code "43") (name "DCF#") (class "Default")
      (node (ref "M2") (pin "4") (pinfunction "DCF#_4") (pintype "output"))
      (node (ref "R29") (pin "1") (pinfunction "1_1") (pintype "passive"))
      (node (ref "R34") (pin "1") (pinfunction "1_1") (pintype "passive"))
    )
    (net (code "44") (name "FT_EECS") (class "Default")
      (node (ref "IC3") (pin "32") (pinfunction "EECS_32") (pintype "bidirectional"))
      (node (ref "IC4") (pin "1") (pinfunction "CS_1") (pintype "input"))
    )
    (net (code "45") (name "FT_EEDATA") (class "Default")
      (node (ref "IC3") (pin "2") (pinfunction "EEDATA_2") (pintype "bidirectional"))
      (node (ref "IC4") (pin "3") (pinfunction "DI_3") (pintype "input"))
      (node (ref "R6") (pin "2") (pinfunction "2_2") (pintype "passive"))
    )
    (net (code "46") (name "FT_EESK") (class "Default")
      (node (ref "IC3") (pin "1") (pinfunction "EESK_1") (pintype "bidirectional"))
      (node (ref "IC4") (pin "2") (pinfunction "SK_2") (pintype "bidirectional"))
    )
    (net (code "47") (name "FT_PWREN#") (class "Default")
      (node (ref "IC3") (pin "15") (pinfunction "PWREN#_15") (pintype "bidirectional"))
      (node (ref "S1") (pin "1") (pinfunction "O_1") (pintype "passive"))
    )
    (net (code "48") (name "FT_RTS#") (class "Default")
      (node (ref "D2") (pin "C") (pinfunction "C_C") (pintype "passive"))
      (node (ref "IC3") (pin "23") (pinfunction "RTS#_23") (pintype "bidirectional"))
    )
    (net (code "49") (name "FT_XTIN") (class "Default")
      (node (ref "C2") (pin "2") (pinfunction "2_2") (pintype "passive"))
      (node (ref "IC3") (pin "27") (pinfunction "XTIN_27") (pintype "bidirectional"))
      (node (ref "Q2") (pin "1") (pinfunction "1_1") (pintype "passive"))
    )
    (net (code "50") (name "FT_XTOUT") (class "Default")
      (node (ref "C3") (pin "1") (pinfunction "1_1") (pintype "passive"))
      (node (ref "IC3") (pin "28") (pinfunction "XTOUT_28") (pintype "bidirectional"))
      (node (ref "Q2") (pin "2") (pinfunction "2_2") (pintype "passive"))
    )
    (net (code "51") (name "GND") (class "Default")
      (node (ref "C1") (pin "1") (pinfunction "1_1") (pintype "passive"))
      (node (ref "C10") (pin "2") (pinfunction "2_2") (pintype "passive"))
      (node (ref "C11") (pin "1") (pinfunction "1_1") (pintype "passive"))
      (node (ref "C12") (pin "1") (pinfunction "1_1") (pintype "passive"))
      (node (ref "C13") (pin "1") (pinfunction "1_1") (pintype "passive"))
      (node (ref "C14") (pin "1") (pinfunction "1_1") (pintype "passive"))
      (node (ref "C15") (pin "-") (pinfunction "-_-") (pintype "passive"))
      (node (ref "C17") (pin "1") (pinfunction "1_1") (pintype "passive"))
      (node (ref "C2") (pin "1") (pinfunction "1_1") (pintype "passive"))
      (node (ref "C3") (pin "2") (pinfunction "2_2") (pintype "passive"))
      (node (ref "C4") (pin "1") (pinfunction "1_1") (pintype "passive"))
      (node (ref "C6") (pin "-") (pinfunction "-_-") (pintype "passive"))
      (node (ref "C7") (pin "-") (pinfunction "-_-") (pintype "passive"))
      (node (ref "C8") (pin "-") (pinfunction "-_-") (pintype "passive"))
      (node (ref "C9") (pin "2") (pinfunction "2_2") (pintype "passive"))
      (node (ref "CON1") (pin "4") (pinfunction "GND_4") (pintype "power_in"))
      (node (ref "GPIO") (pin "10") (pinfunction "10_10") (pintype "passive"))
      (node (ref "H1") (pin "B3,2") (pinfunction "MOUNT_B3,2") (pintype "passive"))
      (node (ref "H2") (pin "B3,2") (pinfunction "MOUNT_B3,2") (pintype "passive"))
      (node (ref "H3") (pin "B3,2") (pinfunction "MOUNT_B3,2") (pintype "passive"))
      (node (ref "H4") (pin "B3,2") (pinfunction "MOUNT_B3,2") (pintype "passive"))
      (node (ref "I2C_3V3") (pin "4") (pinfunction "4_4") (pintype "passive"))
      (node (ref "I2C_5V") (pin "4") (pinfunction "4_4") (pintype "passive"))
      (node (ref "IC1") (pin "20") (pinfunction "GND_20") (pintype "power_in"))
      (node (ref "IC1") (pin "31") (pinfunction "GND_31") (pintype "power_in"))
      (node (ref "IC2") (pin "1") (pinfunction "A0_1") (pintype "input"))
      (node (ref "IC2") (pin "2") (pinfunction "A1_2") (pintype "input"))
      (node (ref "IC2") (pin "3") (pinfunction "A2_3") (pintype "input"))
      (node (ref "IC2") (pin "4") (pinfunction "GND_4") (pintype "power_in"))
      (node (ref "IC2") (pin "7") (pinfunction "WP_7") (pintype "input"))
      (node (ref "IC3") (pin "14") (pinfunction "PWRCTL_14") (pintype "bidirectional"))
      (node (ref "IC3") (pin "17") (pinfunction "GND_17") (pintype "power_in"))
      (node (ref "IC3") (pin "29") (pinfunction "AGND_29") (pintype "power_in"))
      (node (ref "IC3") (pin "31") (pinfunction "TEST_31") (pintype "bidirectional"))
      (node (ref "IC3") (pin "9") (pinfunction "GND_9") (pintype "power_in"))
      (node (ref "IC4") (pin "5") (pinfunction "GND_5") (pintype "power_in"))
      (node (ref "IC4") (pin "7") (pinfunction "DC_7") (pintype "input"))
      (node (ref "IC5") (pin "2") (pinfunction "GND_2") (pintype "power_in"))
      (node (ref "INT") (pin "4") (pinfunction "4_4") (pintype "passive"))
      (node (ref "M1") (pin "1") (pinfunction "GND_1") (pintype "power_in"))
      (node (ref "M1") (pin "10") (pinfunction "DB3_10") (pintype "bidirectional"))
      (node (ref "M1") (pin "7") (pinfunction "DB0_7") (pintype "bidirectional"))
      (node (ref "M1") (pin "8") (pinfunction "DB1_8") (pintype "bidirectional"))
      (node (ref "M1") (pin "9") (pinfunction "DB2_9") (pintype "bidirectional"))
      (node (ref "M2") (pin "1") (pinfunction "GND_1") (pintype "power_in"))
      (node (ref "Q3") (pin "3") (pinfunction "S_3") (pintype "passive"))
      (node (ref "Q4") (pin "2") (pinfunction "E_2") (pintype "passive"))
      (node (ref "Q5") (pin "2") (pinfunction "E_2") (pintype "passive"))
      (node (ref "QG1") (pin "7") (pinfunction "VSS_7") (pintype "power_in"))
      (node (ref "R10") (pin "1") (pinfunction "1_1") (pintype "passive"))
      (node (ref "R21") (pin "1") (pinfunction "1_1") (pintype "passive"))
      (node (ref "R22") (pin "1") (pinfunction "1_1") (pintype "passive"))
      (node (ref "R23") (pin "1") (pinfunction "1_1") (pintype "passive"))
      (node (ref "R24") (pin "1") (pinfunction "1_1") (pintype "passive"))
      (node (ref "R25") (pin "A") (pinfunction "A_A") (pintype "passive"))
      (node (ref "R30") (pin "1") (pinfunction "1_1") (pintype "passive"))
      (node (ref "R9") (pin "1") (pinfunction "1_1") (pintype "passive"))
      (node (ref "S1") (pin "3") (pinfunction "S_3") (pintype "passive"))
      (node (ref "U$1") (pin "3") (pinfunction "3_3") (pintype "bidirectional"))
      (node (ref "U$1") (pin "4") (pinfunction "4_4") (pintype "bidirectional"))
    )
    (net (code "52") (name "I2C_5V_SCL") (class "Default")
      (node (ref "I2C_5V") (pin "2") (pinfunction "2_2") (pintype "passive"))
      (node (ref "IC6") (pin "8") (pinfunction "SCL_8") (pintype "input"))
      (node (ref "Q6") (pin "3") (pinfunction "D_3") (pintype "passive"))
      (node (ref "R41") (pin "1") (pinfunction "1_1") (pintype "passive"))
    )
    (net (code "53") (name "I2C_5V_SDA") (class "Default")
      (node (ref "I2C_5V") (pin "3") (pinfunction "3_3") (pintype "passive"))
      (node (ref "IC6") (pin "7") (pinfunction "SDA_7") (pintype "bidirectional"))
      (node (ref "Q7") (pin "3") (pinfunction "D_3") (pintype "passive"))
      (node (ref "R42") (pin "1") (pinfunction "1_1") (pintype "passive"))
    )
    (net (code "54") (name "LCD_BLA") (class "Default")
      (node (ref "M1") (pin "15") (pinfunction "BLA_15") (pintype "bidirectional"))
      (node (ref "R13") (pin "2") (pinfunction "2_2") (pintype "passive"))
    )
    (net (code "55") (name "LCD_BLK") (class "Default")
      (node (ref "M1") (pin "16") (pinfunction "BLK_16") (pintype "bidirectional"))
      (node (ref "Q3") (pin "2") (pinfunction "D_2") (pintype "passive"))
      (node (ref "Q3") (pin "4") (pinfunction "D_4") (pintype "passive"))
    )
    (net (code "56") (name "LCD_DB4") (class "Default")
      (node (ref "M1") (pin "11") (pinfunction "DB4_11") (pintype "bidirectional"))
      (node (ref "R20") (pin "2") (pinfunction "2_2") (pintype "passive"))
    )
    (net (code "57") (name "LCD_DB5") (class "Default")
      (node (ref "M1") (pin "12") (pinfunction "DB5_12") (pintype "bidirectional"))
      (node (ref "R19") (pin "2") (pinfunction "2_2") (pintype "passive"))
    )
    (net (code "58") (name "LCD_DB6") (class "Default")
      (node (ref "M1") (pin "13") (pinfunction "DB6_13") (pintype "bidirectional"))
      (node (ref "R18") (pin "2") (pinfunction "2_2") (pintype "passive"))
    )
    (net (code "59") (name "LCD_DB7") (class "Default")
      (node (ref "M1") (pin "14") (pinfunction "DB7_14") (pintype "bidirectional"))
      (node (ref "R17") (pin "2") (pinfunction "2_2") (pintype "passive"))
    )
    (net (code "60") (name "LCD_E") (class "Default")
      (node (ref "M1") (pin "6") (pinfunction "E_6") (pintype "bidirectional"))
      (node (ref "R16") (pin "2") (pinfunction "2_2") (pintype "passive"))
    )
    (net (code "61") (name "LCD_RS") (class "Default")
      (node (ref "M1") (pin "4") (pinfunction "RS_4") (pintype "bidirectional"))
      (node (ref "R14") (pin "2") (pinfunction "2_2") (pintype "passive"))
    )
    (net (code "62") (name "LCD_R{slash}W#") (class "Default")
      (node (ref "M1") (pin "5") (pinfunction "R/W#_5") (pintype "bidirectional"))
      (node (ref "R15") (pin "2") (pinfunction "2_2") (pintype "passive"))
    )
    (net (code "63") (name "LCD_VO") (class "Default")
      (node (ref "M1") (pin "3") (pinfunction "VO_3") (pintype "bidirectional"))
      (node (ref "R25") (pin "S") (pinfunction "S_S") (pintype "passive"))
    )
    (net (code "64") (name "Net-(IC2-SDA)") (class "Default")
      (node (ref "IC2") (pin "5") (pinfunction "SDA_5") (pintype "bidirectional"))
      (node (ref "PROG") (pin "3") (pinfunction "3_3") (pintype "passive"))
    )
    (net (code "65") (name "Net-(IC3-3V3OUT)") (class "Default")
      (node (ref "C1") (pin "2") (pinfunction "2_2") (pintype "passive"))
      (node (ref "IC3") (pin "6") (pinfunction "3V3OUT_6") (pintype "power_in"))
    )
    (net (code "66") (name "Net-(IC3-AVCC)") (class "Default")
      (node (ref "C4") (pin "2") (pinfunction "2_2") (pintype "passive"))
      (node (ref "IC3") (pin "30") (pinfunction "AVCC_30") (pintype "power_in"))
      (node (ref "R4") (pin "1") (pinfunction "1_1") (pintype "passive"))
    )
    (net (code "67") (name "Net-(IC3-RSTOUT#)") (class "Default")
      (node (ref "IC3") (pin "5") (pinfunction "RSTOUT#_5") (pintype "bidirectional"))
      (node (ref "R3") (pin "2") (pinfunction "2_2") (pintype "passive"))
    )
    (net (code "68") (name "Net-(IC3-RXLED#)") (class "Default")
      (node (ref "IC3") (pin "11") (pinfunction "RXLED#_11") (pintype "bidirectional"))
      (node (ref "IC3") (pin "12") (pinfunction "TXLED#_12") (pintype "bidirectional"))
      (node (ref "R8") (pin "1") (pinfunction "1_1") (pintype "passive"))
    )
    (net (code "69") (name "Net-(IC3-USBDM)") (class "Default")
      (node (ref "IC3") (pin "8") (pinfunction "USBDM_8") (pintype "bidirectional"))
      (node (ref "R2") (pin "2") (pinfunction "2_2") (pintype "passive"))
    )
    (net (code "70") (name "Net-(IC3-USBDP)") (class "Default")
      (node (ref "IC3") (pin "7") (pinfunction "USBDP_7") (pintype "bidirectional"))
      (node (ref "R1") (pin "2") (pinfunction "2_2") (pintype "passive"))
      (node (ref "R3") (pin "1") (pinfunction "1_1") (pintype "passive"))
    )
    (net (code "71") (name "Net-(IC4-DO)") (class "Default")
      (node (ref "IC4") (pin "4") (pinfunction "DO_4") (pintype "output"))
      (node (ref "R6") (pin "1") (pinfunction "1_1") (pintype "passive"))
      (node (ref "R7") (pin "1") (pinfunction "1_1") (pintype "passive"))
    )
    (net (code "72") (name "Net-(LED1-C)") (class "Default")
      (node (ref "LED1") (pin "K") (pinfunction "C_K") (pintype "passive"))
      (node (ref "Q4") (pin "3") (pinfunction "C_3") (pintype "passive"))
    )
    (net (code "73") (name "Net-(LED1-PadA)") (class "Default")
      (node (ref "LED1") (pin "A") (pinfunction "A_A") (pintype "passive"))
      (node (ref "R37") (pin "2") (pinfunction "2_2") (pintype "passive"))
    )
    (net (code "74") (name "Net-(LED2-C)") (class "Default")
      (node (ref "LED2") (pin "K") (pinfunction "C_K") (pintype "passive"))
      (node (ref "Q5") (pin "3") (pinfunction "C_3") (pintype "passive"))
    )
    (net (code "75") (name "Net-(LED2-PadA)") (class "Default")
      (node (ref "LED2") (pin "A") (pinfunction "A_A") (pintype "passive"))
      (node (ref "R39") (pin "2") (pinfunction "2_2") (pintype "passive"))
    )
    (net (code "76") (name "Net-(PWR_3V3-C)") (class "Default")
      (node (ref "PWR_3V3") (pin "K") (pinfunction "C_K") (pintype "passive"))
      (node (ref "R9") (pin "2") (pinfunction "2_2") (pintype "passive"))
    )
    (net (code "77") (name "Net-(PWR_3V3_S-C)") (class "Default")
      (node (ref "PWR_3V3_S") (pin "K") (pinfunction "C_K") (pintype "passive"))
      (node (ref "R10") (pin "2") (pinfunction "2_2") (pintype "passive"))
    )
    (net (code "78") (name "Net-(Q1-G)") (class "Default")
      (node (ref "C5") (pin "1") (pinfunction "1_1") (pintype "passive"))
      (node (ref "Q1") (pin "1") (pinfunction "G_1") (pintype "passive"))
      (node (ref "R43") (pin "1") (pinfunction "1_1") (pintype "passive"))
      (node (ref "R5") (pin "1") (pinfunction "1_1") (pintype "passive"))
    )
    (net (code "79") (name "Net-(Q3-G)") (class "Default")
      (node (ref "Q3") (pin "1") (pinfunction "G_1") (pintype "passive"))
      (node (ref "R12") (pin "2") (pinfunction "2_2") (pintype "passive"))
    )
    (net (code "80") (name "Net-(Q4-B)") (class "Default")
      (node (ref "Q4") (pin "1") (pinfunction "B_1") (pintype "passive"))
      (node (ref "R38") (pin "2") (pinfunction "2_2") (pintype "passive"))
    )
    (net (code "81") (name "Net-(Q5-B)") (class "Default")
      (node (ref "Q5") (pin "1") (pinfunction "B_1") (pintype "passive"))
      (node (ref "R40") (pin "2") (pinfunction "2_2") (pintype "passive"))
    )
    (net (code "82") (name "Net-(UART-C)") (class "Default")
      (node (ref "R8") (pin "2") (pinfunction "2_2") (pintype "passive"))
      (node (ref "UART") (pin "K") (pinfunction "C_K") (pintype "passive"))
    )
    (net (code "83") (name "PRES_REF") (class "Default")
      (node (ref "IC6") (pin "4") (pinfunction "CH2-_4") (pintype "bidirectional"))
      (node (ref "R35") (pin "2") (pinfunction "2_2") (pintype "passive"))
    )
    (net (code "84") (name "PRES_SENSE") (class "Default")
      (node (ref "C22") (pin "2") (pinfunction "2_2") (pintype "passive"))
      (node (ref "IC6") (pin "3") (pinfunction "CH2+_3") (pintype "bidirectional"))
      (node (ref "V1") (pin "1") (pinfunction "VO+_1") (pintype "passive"))
    )
    (net (code "85") (name "PWREN3V3#") (class "Default")
      (node (ref "R5") (pin "2") (pinfunction "2_2") (pintype "passive"))
      (node (ref "S1") (pin "2") (pinfunction "P_2") (pintype "passive"))
    )
    (net (code "86") (name "TEMP_REF") (class "Default")
      (node (ref "IC6") (pin "2") (pinfunction "CH1-_2") (pintype "bidirectional"))
      (node (ref "R36") (pin "2") (pinfunction "2_2") (pintype "passive"))
    )
    (net (code "87") (name "TEMP_SENSE") (class "Default")
      (node (ref "IC6") (pin "1") (pinfunction "CH1+_1") (pintype "bidirectional"))
      (node (ref "R31") (pin "1") (pinfunction "1_1") (pintype "passive"))
      (node (ref "R32") (pin "1") (pinfunction "1_1") (pintype "passive"))
    )
    (net (code "88") (name "USB_DM") (class "Default")
      (node (ref "CON1") (pin "2") (pinfunction "D-_2") (pintype "bidirectional"))
      (node (ref "R2") (pin "1") (pinfunction "1_1") (pintype "passive"))
    )
    (net (code "89") (name "USB_DP") (class "Default")
      (node (ref "CON1") (pin "3") (pinfunction "D+_3") (pintype "bidirectional"))
      (node (ref "R1") (pin "1") (pinfunction "1_1") (pintype "passive"))
    )
    (net (code "90") (name "unconnected-(CON1-KEY-PadNC)") (class "Default")
      (node (ref "CON1") (pin "NC") (pinfunction "KEY_NC") (pintype "passive"))
    )
    (net (code "91") (name "unconnected-(CON1-SHIELD-PadSHIELD@1)") (class "Default")
      (node (ref "CON1") (pin "SHIELD@1") (pinfunction "SHIELD_SHIELD@1") (pintype "passive"))
    )
    (net (code "92") (name "unconnected-(CON1-SHIELD-PadSHIELD@2)") (class "Default")
      (node (ref "CON1") (pin "SHIELD@2") (pinfunction "SHIELD_SHIELD@2") (pintype "passive"))
    )
    (net (code "93") (name "unconnected-(IC1-ALE-Pad30)") (class "Default")
      (node (ref "IC1") (pin "30") (pinfunction "ALE_30") (pintype "bidirectional"))
    )
    (net (code "94") (name "unconnected-(IC1-SRAM_CS-Pad29)") (class "Default")
      (node (ref "IC1") (pin "29") (pinfunction "SRAM_CS_29") (pintype "bidirectional"))
    )
    (net (code "95") (name "unconnected-(IC3-DCD#-Pad19)") (class "Default")
      (node (ref "IC3") (pin "19") (pinfunction "DCD#_19") (pintype "bidirectional"))
    )
    (net (code "96") (name "unconnected-(IC3-DSR#-Pad20)") (class "Default")
      (node (ref "IC3") (pin "20") (pinfunction "DSR#_20") (pintype "bidirectional"))
    )
    (net (code "97") (name "unconnected-(IC3-DTR#-Pad21)") (class "Default")
      (node (ref "IC3") (pin "21") (pinfunction "DTR#_21") (pintype "bidirectional"))
    )
    (net (code "98") (name "unconnected-(IC3-RI#-Pad18)") (class "Default")
      (node (ref "IC3") (pin "18") (pinfunction "RI#_18") (pintype "bidirectional"))
    )
    (net (code "99") (name "unconnected-(IC3-SLEEP#-Pad10)") (class "Default")
      (node (ref "IC3") (pin "10") (pinfunction "SLEEP#_10") (pintype "bidirectional"))
    )
    (net (code "100") (name "unconnected-(IC3-TXDEN-Pad16)") (class "Default")
      (node (ref "IC3") (pin "16") (pinfunction "TXDEN_16") (pintype "bidirectional"))
    )
    (net (code "101") (name "unconnected-(PROG-Pad1)") (class "Default")
      (node (ref "PROG") (pin "1") (pinfunction "1_1") (pintype "passive"))
    )
    (net (code "102") (name "~{CD_RESET}") (class "Default")
      (node (ref "C15") (pin "+") (pinfunction "+_+") (pintype "passive"))
      (node (ref "D1") (pin "A") (pinfunction "A_A") (pintype "passive"))
      (node (ref "D2") (pin "A") (pinfunction "A_A") (pintype "passive"))
      (node (ref "IC1") (pin "9") (pinfunction "RESET_9") (pintype "input"))
      (node (ref "R11") (pin "2") (pinfunction "2_2") (pintype "passive"))
      (node (ref "U$1") (pin "1") (pinfunction "1_1") (pintype "bidirectional"))
      (node (ref "U$1") (pin "2") (pinfunction "2_2") (pintype "bidirectional"))
    )
  )
)
